# 13_Zynq_PL.net
KiCad netlist of a schematic drawn in Altium Designer
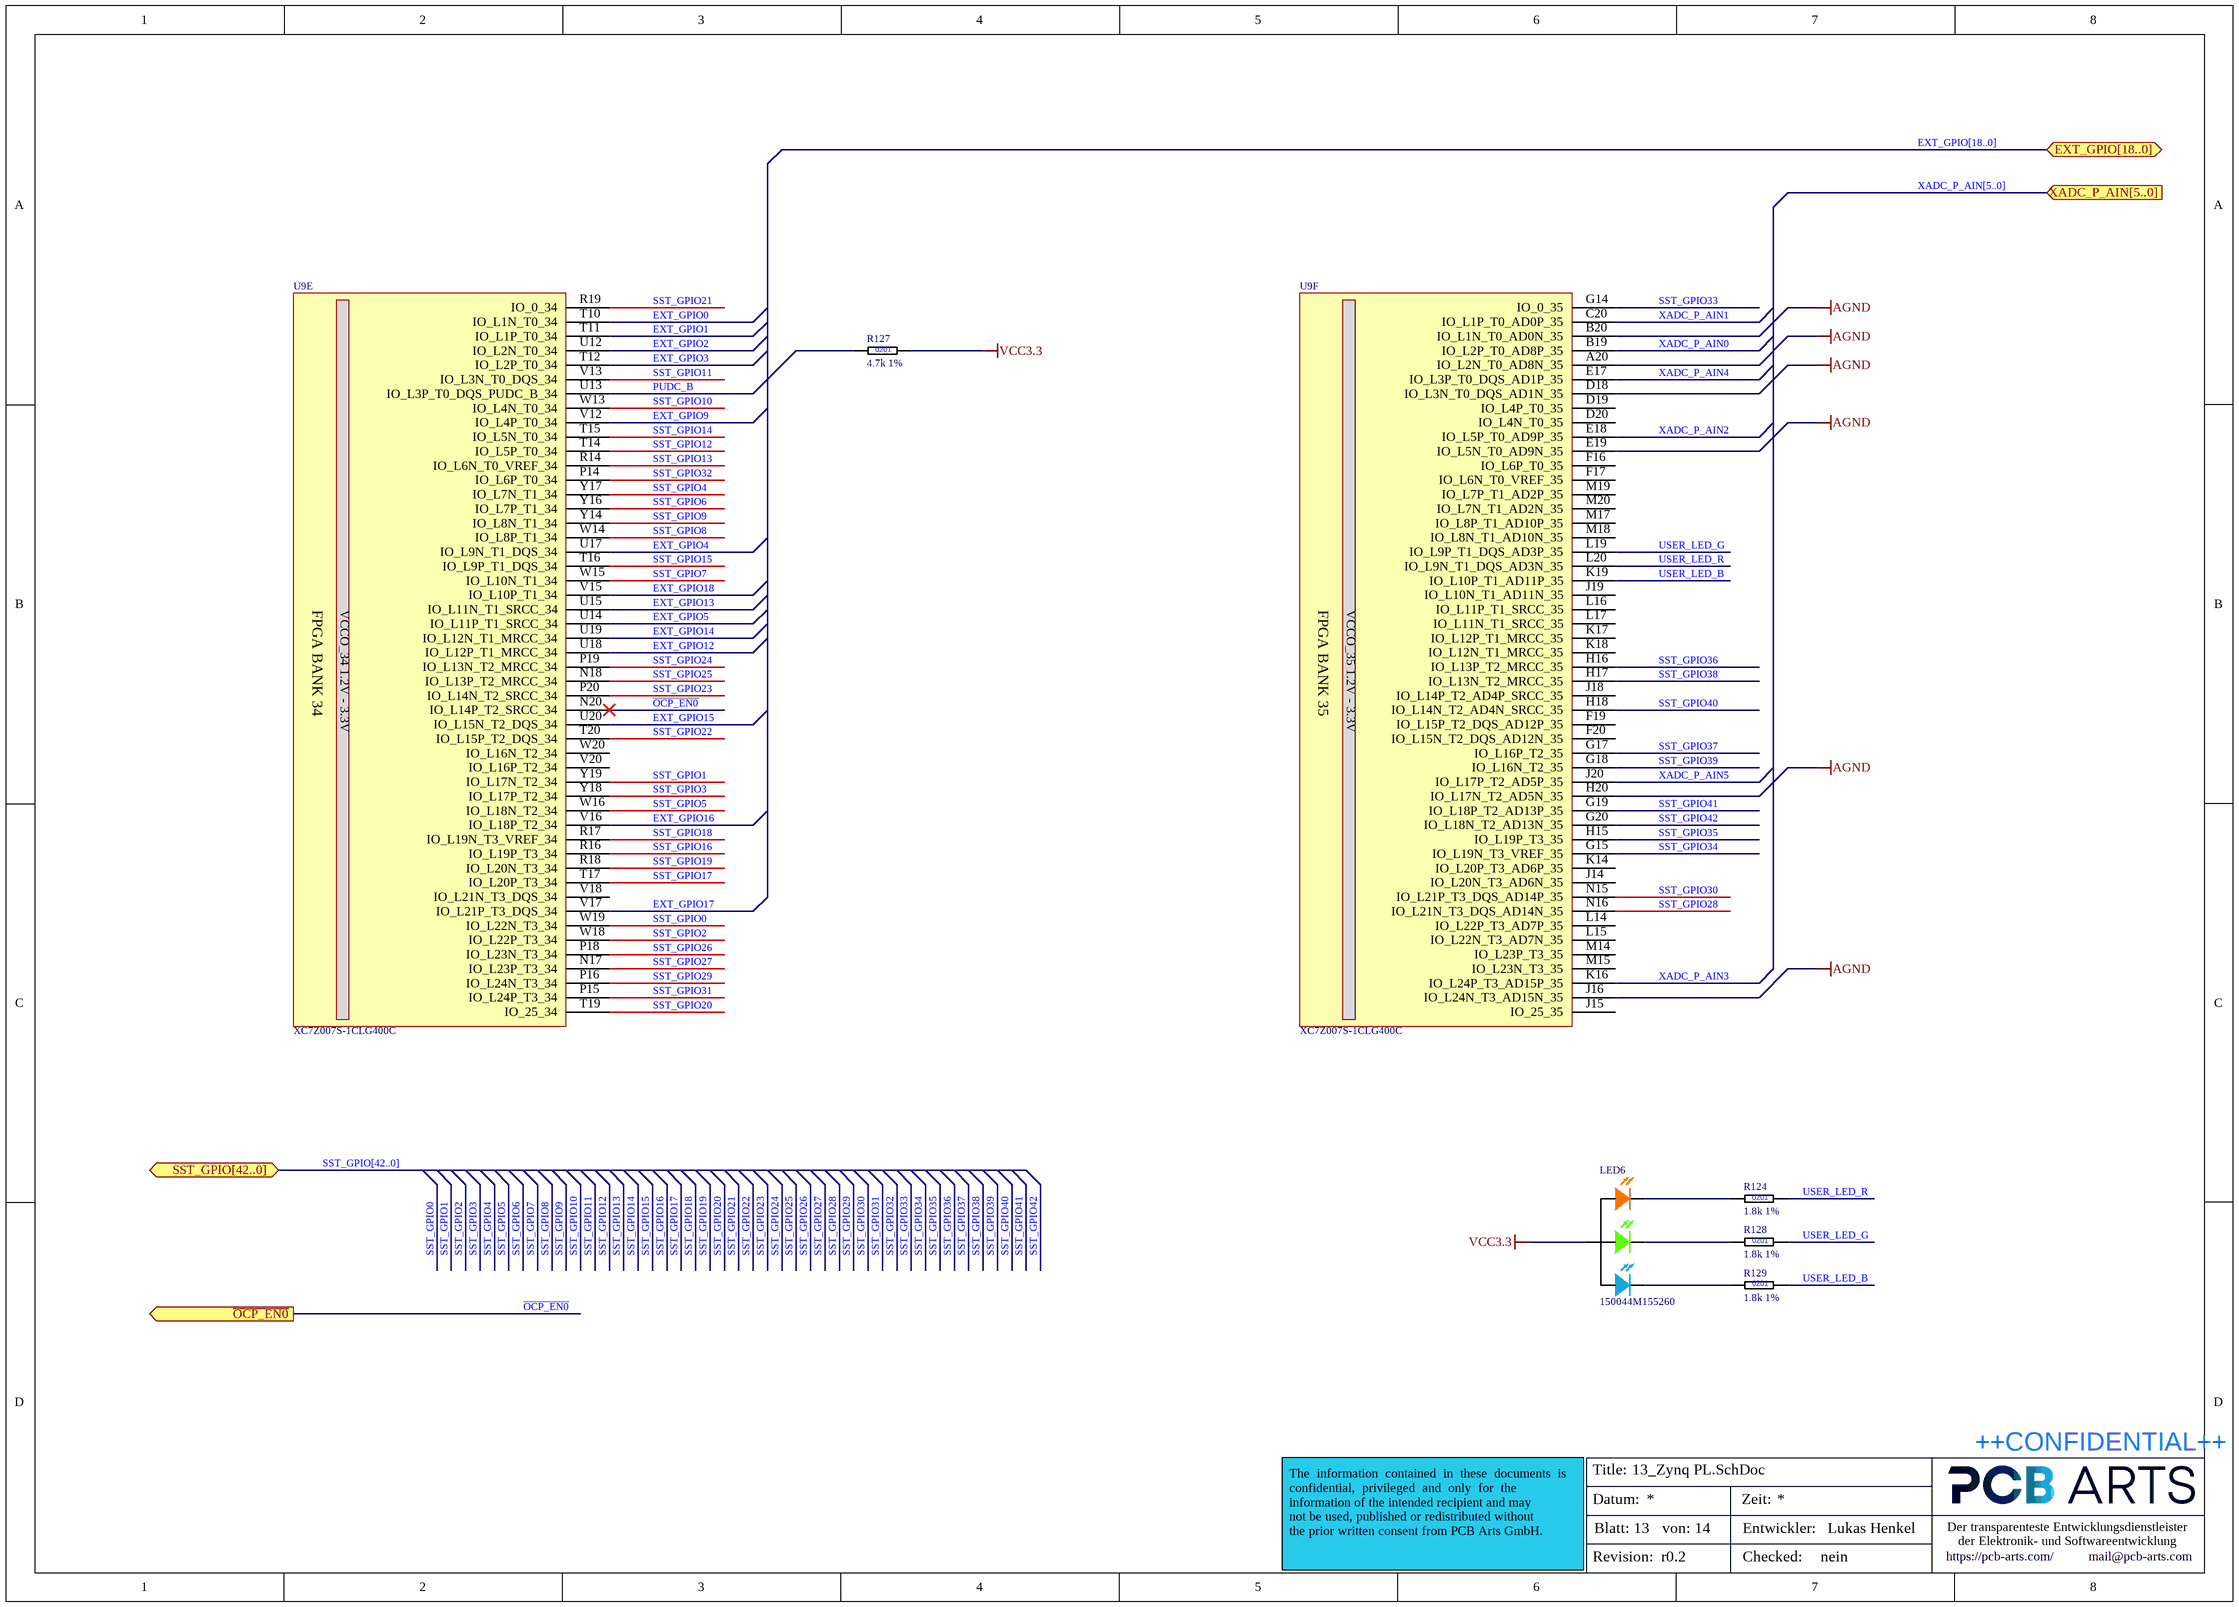
[diagram p0: 13_Zynq PL.SchDoc]

(export (version "E")
  (design (tool "Eeschema 10.0.6"))
  (components
    (comp (ref "LED6")
      (value "150044M155260")
      (footprint "Zynq-Feather-HD:WL-SFCC SMT")
      (description "Standard LEDs - SMD WL-SFCC SMT LED Full-color Chip")
      (libsource (lib "Zynq-Feather-HD") (part "150044M155260_SMD WL-SFCC SMT LED Full-color Chip"))
    )
    (comp (ref "R124")
      (value "1.8k 1%")
      (footprint "Zynq-Feather-HD:RESC0603X03L")
      (description "Thick Film Resistors - SMD 1.8K OHM 1%")
      (libsource (lib "Zynq-Feather-HD") (part "RES_0201_1.8k_1%"))
    )
    (comp (ref "R127")
      (value "4.7k 1%")
      (footprint "Zynq-Feather-HD:RESC0603X03L")
      (description "Thick Film Resistors - SMD 4.7K OHM 1%")
      (libsource (lib "Zynq-Feather-HD") (part "RES_0201_4.7k_1%"))
    )
    (comp (ref "R128")
      (value "1.8k 1%")
      (footprint "Zynq-Feather-HD:RESC0603X03L")
      (description "Thick Film Resistors - SMD 1.8K OHM 1%")
      (libsource (lib "Zynq-Feather-HD") (part "RES_0201_1.8k_1%"))
    )
    (comp (ref "R129")
      (value "1.8k 1%")
      (footprint "Zynq-Feather-HD:RESC0603X03L")
      (description "Thick Film Resistors - SMD 1.8K OHM 1%")
      (libsource (lib "Zynq-Feather-HD") (part "RES_0201_1.8k_1%"))
    )
    (comp (ref "U9")
      (value "XC7Z007S-1CLG400C")
      (footprint "Zynq-Feather-HD:BGA400C80P20X20_1700X1700X160")
      (description "XC7Z007S-1CLG400C_Processors - Application Specialised")
      (libsource (lib "Zynq-Feather-HD") (part "XC7Z007S-1CLG400C_Processors - Application Specialised"))
    )
  )
  (nets
    (net (code "6") (name "/EXT_GPIO0") (class "Default")
      (node (ref "U9") (pin "T10") (pinfunction "IO_L1N_T0_34_T10") (pintype "passive"))
    )
    (net (code "7") (name "/EXT_GPIO1") (class "Default")
      (node (ref "U9") (pin "T11") (pinfunction "IO_L1P_T0_34_T11") (pintype "passive"))
    )
    (net (code "8") (name "/EXT_GPIO2") (class "Default")
      (node (ref "U9") (pin "U12") (pinfunction "IO_L2N_T0_34_U12") (pintype "passive"))
    )
    (net (code "9") (name "/EXT_GPIO3") (class "Default")
      (node (ref "U9") (pin "T12") (pinfunction "IO_L2P_T0_34_T12") (pintype "passive"))
    )
    (net (code "10") (name "/EXT_GPIO4") (class "Default")
      (node (ref "U9") (pin "U17") (pinfunction "IO_L9N_T1_DQS_34_U17") (pintype "passive"))
    )
    (net (code "11") (name "/EXT_GPIO5") (class "Default")
      (node (ref "U9") (pin "U14") (pinfunction "IO_L11P_T1_SRCC_34_U14") (pintype "passive"))
    )
    (net (code "12") (name "/EXT_GPIO9") (class "Default")
      (node (ref "U9") (pin "V12") (pinfunction "IO_L4P_T0_34_V12") (pintype "passive"))
    )
    (net (code "13") (name "/EXT_GPIO12") (class "Default")
      (node (ref "U9") (pin "U18") (pinfunction "IO_L12P_T1_MRCC_34_U18") (pintype "passive"))
    )
    (net (code "14") (name "/EXT_GPIO13") (class "Default")
      (node (ref "U9") (pin "U15") (pinfunction "IO_L11N_T1_SRCC_34_U15") (pintype "passive"))
    )
    (net (code "15") (name "/EXT_GPIO14") (class "Default")
      (node (ref "U9") (pin "U19") (pinfunction "IO_L12N_T1_MRCC_34_U19") (pintype "passive"))
    )
    (net (code "16") (name "/EXT_GPIO15") (class "Default")
      (node (ref "U9") (pin "U20") (pinfunction "IO_L15N_T2_DQS_34_U20") (pintype "passive"))
    )
    (net (code "17") (name "/EXT_GPIO16") (class "Default")
      (node (ref "U9") (pin "V16") (pinfunction "IO_L18P_T2_34_V16") (pintype "passive"))
    )
    (net (code "18") (name "/EXT_GPIO17") (class "Default")
      (node (ref "U9") (pin "V17") (pinfunction "IO_L21P_T3_DQS_34_V17") (pintype "passive"))
    )
    (net (code "19") (name "/EXT_GPIO18") (class "Default")
      (node (ref "U9") (pin "V15") (pinfunction "IO_L10P_T1_34_V15") (pintype "passive"))
    )
    (net (code "21") (name "/PUDC_B") (class "Default")
      (node (ref "R127") (pin "1") (pinfunction "1_1") (pintype "passive"))
      (node (ref "U9") (pin "U13") (pinfunction "IO_L3P_T0_DQS_PUDC_B_34_U13") (pintype "passive"))
    )
    (net (code "22") (name "/SST_GPIO0") (class "Default")
      (node (ref "U9") (pin "W19") (pinfunction "IO_L22N_T3_34_W19") (pintype "passive"))
    )
    (net (code "23") (name "/SST_GPIO1") (class "Default")
      (node (ref "U9") (pin "Y19") (pinfunction "IO_L17N_T2_34_Y19") (pintype "passive"))
    )
    (net (code "24") (name "/SST_GPIO2") (class "Default")
      (node (ref "U9") (pin "W18") (pinfunction "IO_L22P_T3_34_W18") (pintype "passive"))
    )
    (net (code "25") (name "/SST_GPIO3") (class "Default")
      (node (ref "U9") (pin "Y18") (pinfunction "IO_L17P_T2_34_Y18") (pintype "passive"))
    )
    (net (code "26") (name "/SST_GPIO4") (class "Default")
      (node (ref "U9") (pin "Y17") (pinfunction "IO_L7N_T1_34_Y17") (pintype "passive"))
    )
    (net (code "27") (name "/SST_GPIO5") (class "Default")
      (node (ref "U9") (pin "W16") (pinfunction "IO_L18N_T2_34_W16") (pintype "passive"))
    )
    (net (code "28") (name "/SST_GPIO6") (class "Default")
      (node (ref "U9") (pin "Y16") (pinfunction "IO_L7P_T1_34_Y16") (pintype "passive"))
    )
    (net (code "29") (name "/SST_GPIO7") (class "Default")
      (node (ref "U9") (pin "W15") (pinfunction "IO_L10N_T1_34_W15") (pintype "passive"))
    )
    (net (code "30") (name "/SST_GPIO8") (class "Default")
      (node (ref "U9") (pin "W14") (pinfunction "IO_L8P_T1_34_W14") (pintype "passive"))
    )
    (net (code "31") (name "/SST_GPIO9") (class "Default")
      (node (ref "U9") (pin "Y14") (pinfunction "IO_L8N_T1_34_Y14") (pintype "passive"))
    )
    (net (code "32") (name "/SST_GPIO10") (class "Default")
      (node (ref "U9") (pin "W13") (pinfunction "IO_L4N_T0_34_W13") (pintype "passive"))
    )
    (net (code "33") (name "/SST_GPIO11") (class "Default")
      (node (ref "U9") (pin "V13") (pinfunction "IO_L3N_T0_DQS_34_V13") (pintype "passive"))
    )
    (net (code "34") (name "/SST_GPIO12") (class "Default")
      (node (ref "U9") (pin "T14") (pinfunction "IO_L5P_T0_34_T14") (pintype "passive"))
    )
    (net (code "35") (name "/SST_GPIO13") (class "Default")
      (node (ref "U9") (pin "R14") (pinfunction "IO_L6N_T0_VREF_34_R14") (pintype "passive"))
    )
    (net (code "36") (name "/SST_GPIO14") (class "Default")
      (node (ref "U9") (pin "T15") (pinfunction "IO_L5N_T0_34_T15") (pintype "passive"))
    )
    (net (code "37") (name "/SST_GPIO15") (class "Default")
      (node (ref "U9") (pin "T16") (pinfunction "IO_L9P_T1_DQS_34_T16") (pintype "passive"))
    )
    (net (code "38") (name "/SST_GPIO16") (class "Default")
      (node (ref "U9") (pin "R16") (pinfunction "IO_L19P_T3_34_R16") (pintype "passive"))
    )
    (net (code "39") (name "/SST_GPIO17") (class "Default")
      (node (ref "U9") (pin "T17") (pinfunction "IO_L20P_T3_34_T17") (pintype "passive"))
    )
    (net (code "40") (name "/SST_GPIO18") (class "Default")
      (node (ref "U9") (pin "R17") (pinfunction "IO_L19N_T3_VREF_34_R17") (pintype "passive"))
    )
    (net (code "41") (name "/SST_GPIO19") (class "Default")
      (node (ref "U9") (pin "R18") (pinfunction "IO_L20N_T3_34_R18") (pintype "passive"))
    )
    (net (code "42") (name "/SST_GPIO20") (class "Default")
      (node (ref "U9") (pin "T19") (pinfunction "IO_25_34_T19") (pintype "passive"))
    )
    (net (code "43") (name "/SST_GPIO21") (class "Default")
      (node (ref "U9") (pin "R19") (pinfunction "IO_0_34_R19") (pintype "passive"))
    )
    (net (code "44") (name "/SST_GPIO22") (class "Default")
      (node (ref "U9") (pin "T20") (pinfunction "IO_L15P_T2_DQS_34_T20") (pintype "passive"))
    )
    (net (code "45") (name "/SST_GPIO23") (class "Default")
      (node (ref "U9") (pin "P20") (pinfunction "IO_L14N_T2_SRCC_34_P20") (pintype "passive"))
    )
    (net (code "46") (name "/SST_GPIO24") (class "Default")
      (node (ref "U9") (pin "P19") (pinfunction "IO_L13N_T2_MRCC_34_P19") (pintype "passive"))
    )
    (net (code "47") (name "/SST_GPIO25") (class "Default")
      (node (ref "U9") (pin "N18") (pinfunction "IO_L13P_T2_MRCC_34_N18") (pintype "passive"))
    )
    (net (code "48") (name "/SST_GPIO26") (class "Default")
      (node (ref "U9") (pin "P18") (pinfunction "IO_L23N_T3_34_P18") (pintype "passive"))
    )
    (net (code "49") (name "/SST_GPIO27") (class "Default")
      (node (ref "U9") (pin "N17") (pinfunction "IO_L23P_T3_34_N17") (pintype "passive"))
    )
    (net (code "50") (name "/SST_GPIO28") (class "Default")
      (node (ref "U9") (pin "N16") (pinfunction "IO_L21N_T3_DQS_AD14N_35_N16") (pintype "passive"))
    )
    (net (code "51") (name "/SST_GPIO29") (class "Default")
      (node (ref "U9") (pin "P16") (pinfunction "IO_L24N_T3_34_P16") (pintype "passive"))
    )
    (net (code "52") (name "/SST_GPIO30") (class "Default")
      (node (ref "U9") (pin "N15") (pinfunction "IO_L21P_T3_DQS_AD14P_35_N15") (pintype "passive"))
    )
    (net (code "53") (name "/SST_GPIO31") (class "Default")
      (node (ref "U9") (pin "P15") (pinfunction "IO_L24P_T3_34_P15") (pintype "passive"))
    )
    (net (code "54") (name "/SST_GPIO32") (class "Default")
      (node (ref "U9") (pin "P14") (pinfunction "IO_L6P_T0_34_P14") (pintype "passive"))
    )
    (net (code "55") (name "/SST_GPIO33") (class "Default")
      (node (ref "U9") (pin "G14") (pinfunction "IO_0_35_G14") (pintype "passive"))
    )
    (net (code "56") (name "/SST_GPIO34") (class "Default")
      (node (ref "U9") (pin "G15") (pinfunction "IO_L19N_T3_VREF_35_G15") (pintype "passive"))
    )
    (net (code "57") (name "/SST_GPIO35") (class "Default")
      (node (ref "U9") (pin "H15") (pinfunction "IO_L19P_T3_35_H15") (pintype "passive"))
    )
    (net (code "58") (name "/SST_GPIO36") (class "Default")
      (node (ref "U9") (pin "H16") (pinfunction "IO_L13P_T2_MRCC_35_H16") (pintype "passive"))
    )
    (net (code "59") (name "/SST_GPIO37") (class "Default")
      (node (ref "U9") (pin "G17") (pinfunction "IO_L16P_T2_35_G17") (pintype "passive"))
    )
    (net (code "60") (name "/SST_GPIO38") (class "Default")
      (node (ref "U9") (pin "H17") (pinfunction "IO_L13N_T2_MRCC_35_H17") (pintype "passive"))
    )
    (net (code "61") (name "/SST_GPIO39") (class "Default")
      (node (ref "U9") (pin "G18") (pinfunction "IO_L16N_T2_35_G18") (pintype "passive"))
    )
    (net (code "62") (name "/SST_GPIO40") (class "Default")
      (node (ref "U9") (pin "H18") (pinfunction "IO_L14N_T2_AD4N_SRCC_35_H18") (pintype "passive"))
    )
    (net (code "63") (name "/SST_GPIO41") (class "Default")
      (node (ref "U9") (pin "G19") (pinfunction "IO_L18P_T2_AD13P_35_G19") (pintype "passive"))
    )
    (net (code "64") (name "/SST_GPIO42") (class "Default")
      (node (ref "U9") (pin "G20") (pinfunction "IO_L18N_T2_AD13N_35_G20") (pintype "passive"))
    )
    (net (code "66") (name "/USER_LED_B") (class "Default")
      (node (ref "R129") (pin "2") (pinfunction "2_2") (pintype "passive"))
      (node (ref "U9") (pin "K19") (pinfunction "IO_L10P_T1_AD11P_35_K19") (pintype "passive"))
    )
    (net (code "67") (name "/USER_LED_G") (class "Default")
      (node (ref "R128") (pin "2") (pinfunction "2_2") (pintype "passive"))
      (node (ref "U9") (pin "L19") (pinfunction "IO_L9P_T1_DQS_AD3P_35_L19") (pintype "passive"))
    )
    (net (code "68") (name "/USER_LED_R") (class "Default")
      (node (ref "R124") (pin "2") (pinfunction "2_2") (pintype "passive"))
      (node (ref "U9") (pin "L20") (pinfunction "IO_L9N_T1_DQS_AD3N_35_L20") (pintype "passive"))
    )
    (net (code "69") (name "/XADC_P_AIN0") (class "Default")
      (node (ref "U9") (pin "B19") (pinfunction "IO_L2P_T0_AD8P_35_B19") (pintype "passive"))
    )
    (net (code "70") (name "/XADC_P_AIN1") (class "Default")
      (node (ref "U9") (pin "C20") (pinfunction "IO_L1P_T0_AD0P_35_C20") (pintype "passive"))
    )
    (net (code "71") (name "/XADC_P_AIN2") (class "Default")
      (node (ref "U9") (pin "E18") (pinfunction "IO_L5P_T0_AD9P_35_E18") (pintype "passive"))
    )
    (net (code "72") (name "/XADC_P_AIN3") (class "Default")
      (node (ref "U9") (pin "K16") (pinfunction "IO_L24P_T3_AD15P_35_K16") (pintype "passive"))
    )
    (net (code "73") (name "/XADC_P_AIN4") (class "Default")
      (node (ref "U9") (pin "E17") (pinfunction "IO_L3P_T0_DQS_AD1P_35_E17") (pintype "passive"))
    )
    (net (code "74") (name "/XADC_P_AIN5") (class "Default")
      (node (ref "U9") (pin "J20") (pinfunction "IO_L17P_T2_AD5P_35_J20") (pintype "passive"))
    )
    (net (code "76") (name "/~{OCP_EN0}") (class "Default")
      (node (ref "U9") (pin "N20") (pinfunction "IO_L14P_T2_SRCC_34_N20") (pintype "passive"))
    )
    (net (code "77") (name "AGND") (class "Default")
      (node (ref "U9") (pin "A20") (pinfunction "IO_L2N_T0_AD8N_35_A20") (pintype "passive"))
      (node (ref "U9") (pin "B20") (pinfunction "IO_L1N_T0_AD0N_35_B20") (pintype "passive"))
      (node (ref "U9") (pin "D18") (pinfunction "IO_L3N_T0_DQS_AD1N_35_D18") (pintype "passive"))
      (node (ref "U9") (pin "E19") (pinfunction "IO_L5N_T0_AD9N_35_E19") (pintype "passive"))
      (node (ref "U9") (pin "H20") (pinfunction "IO_L17N_T2_AD5N_35_H20") (pintype "passive"))
      (node (ref "U9") (pin "J16") (pinfunction "IO_L24N_T3_AD15N_35_J16") (pintype "passive"))
    )
    (net (code "78") (name "Net-(LED6-Pad2)") (class "Default")
      (node (ref "LED6") (pin "2") (pinfunction "2_2") (pintype "passive"))
      (node (ref "R124") (pin "1") (pinfunction "1_1") (pintype "passive"))
    )
    (net (code "79") (name "Net-(LED6-Pad3)") (class "Default")
      (node (ref "LED6") (pin "3") (pinfunction "3_3") (pintype "passive"))
      (node (ref "R128") (pin "1") (pinfunction "1_1") (pintype "passive"))
    )
    (net (code "80") (name "Net-(LED6-Pad4)") (class "Default")
      (node (ref "LED6") (pin "4") (pinfunction "4_4") (pintype "passive"))
      (node (ref "R129") (pin "1") (pinfunction "1_1") (pintype "passive"))
    )
    (net (code "81") (name "VCC3.3") (class "Default")
      (node (ref "LED6") (pin "1") (pinfunction "1_1") (pintype "passive"))
      (node (ref "R127") (pin "2") (pinfunction "2_2") (pintype "passive"))
    )
    (net (code "82") (name "unconnected-(U9E-IO_L16N_T2_34-PadW20)") (class "Default")
      (node (ref "U9") (pin "W20") (pinfunction "IO_L16N_T2_34_W20") (pintype "passive"))
    )
    (net (code "83") (name "unconnected-(U9E-IO_L16P_T2_34-PadV20)") (class "Default")
      (node (ref "U9") (pin "V20") (pinfunction "IO_L16P_T2_34_V20") (pintype "passive"))
    )
    (net (code "84") (name "unconnected-(U9E-IO_L21N_T3_DQS_34-PadV18)") (class "Default")
      (node (ref "U9") (pin "V18") (pinfunction "IO_L21N_T3_DQS_34_V18") (pintype "passive"))
    )
    (net (code "85") (name "unconnected-(U9F-IO_25_35-PadJ15)") (class "Default")
      (node (ref "U9") (pin "J15") (pinfunction "IO_25_35_J15") (pintype "passive"))
    )
    (net (code "86") (name "unconnected-(U9F-IO_L4N_T0_35-PadD20)") (class "Default")
      (node (ref "U9") (pin "D20") (pinfunction "IO_L4N_T0_35_D20") (pintype "passive"))
    )
    (net (code "87") (name "unconnected-(U9F-IO_L4P_T0_35-PadD19)") (class "Default")
      (node (ref "U9") (pin "D19") (pinfunction "IO_L4P_T0_35_D19") (pintype "passive"))
    )
    (net (code "88") (name "unconnected-(U9F-IO_L6N_T0_VREF_35-PadF17)") (class "Default")
      (node (ref "U9") (pin "F17") (pinfunction "IO_L6N_T0_VREF_35_F17") (pintype "passive"))
    )
    (net (code "89") (name "unconnected-(U9F-IO_L6P_T0_35-PadF16)") (class "Default")
      (node (ref "U9") (pin "F16") (pinfunction "IO_L6P_T0_35_F16") (pintype "passive"))
    )
    (net (code "90") (name "unconnected-(U9F-IO_L7N_T1_AD2N_35-PadM20)") (class "Default")
      (node (ref "U9") (pin "M20") (pinfunction "IO_L7N_T1_AD2N_35_M20") (pintype "passive"))
    )
    (net (code "91") (name "unconnected-(U9F-IO_L7P_T1_AD2P_35-PadM19)") (class "Default")
      (node (ref "U9") (pin "M19") (pinfunction "IO_L7P_T1_AD2P_35_M19") (pintype "passive"))
    )
    (net (code "92") (name "unconnected-(U9F-IO_L8N_T1_AD10N_35-PadM18)") (class "Default")
      (node (ref "U9") (pin "M18") (pinfunction "IO_L8N_T1_AD10N_35_M18") (pintype "passive"))
    )
    (net (code "93") (name "unconnected-(U9F-IO_L8P_T1_AD10P_35-PadM17)") (class "Default")
      (node (ref "U9") (pin "M17") (pinfunction "IO_L8P_T1_AD10P_35_M17") (pintype "passive"))
    )
    (net (code "94") (name "unconnected-(U9F-IO_L10N_T1_AD11N_35-PadJ19)") (class "Default")
      (node (ref "U9") (pin "J19") (pinfunction "IO_L10N_T1_AD11N_35_J19") (pintype "passive"))
    )
    (net (code "95") (name "unconnected-(U9F-IO_L11N_T1_SRCC_35-PadL17)") (class "Default")
      (node (ref "U9") (pin "L17") (pinfunction "IO_L11N_T1_SRCC_35_L17") (pintype "passive"))
    )
    (net (code "96") (name "unconnected-(U9F-IO_L11P_T1_SRCC_35-PadL16)") (class "Default")
      (node (ref "U9") (pin "L16") (pinfunction "IO_L11P_T1_SRCC_35_L16") (pintype "passive"))
    )
    (net (code "97") (name "unconnected-(U9F-IO_L12N_T1_MRCC_35-PadK18)") (class "Default")
      (node (ref "U9") (pin "K18") (pinfunction "IO_L12N_T1_MRCC_35_K18") (pintype "passive"))
    )
    (net (code "98") (name "unconnected-(U9F-IO_L12P_T1_MRCC_35-PadK17)") (class "Default")
      (node (ref "U9") (pin "K17") (pinfunction "IO_L12P_T1_MRCC_35_K17") (pintype "passive"))
    )
    (net (code "99") (name "unconnected-(U9F-IO_L14P_T2_AD4P_SRCC_35-PadJ18)") (class "Default")
      (node (ref "U9") (pin "J18") (pinfunction "IO_L14P_T2_AD4P_SRCC_35_J18") (pintype "passive"))
    )
    (net (code "100") (name "unconnected-(U9F-IO_L15N_T2_DQS_AD12N_35-PadF20)") (class "Default")
      (node (ref "U9") (pin "F20") (pinfunction "IO_L15N_T2_DQS_AD12N_35_F20") (pintype "passive"))
    )
    (net (code "101") (name "unconnected-(U9F-IO_L15P_T2_DQS_AD12P_35-PadF19)") (class "Default")
      (node (ref "U9") (pin "F19") (pinfunction "IO_L15P_T2_DQS_AD12P_35_F19") (pintype "passive"))
    )
    (net (code "102") (name "unconnected-(U9F-IO_L20N_T3_AD6N_35-PadJ14)") (class "Default")
      (node (ref "U9") (pin "J14") (pinfunction "IO_L20N_T3_AD6N_35_J14") (pintype "passive"))
    )
    (net (code "103") (name "unconnected-(U9F-IO_L20P_T3_AD6P_35-PadK14)") (class "Default")
      (node (ref "U9") (pin "K14") (pinfunction "IO_L20P_T3_AD6P_35_K14") (pintype "passive"))
    )
    (net (code "104") (name "unconnected-(U9F-IO_L22N_T3_AD7N_35-PadL15)") (class "Default")
      (node (ref "U9") (pin "L15") (pinfunction "IO_L22N_T3_AD7N_35_L15") (pintype "passive"))
    )
    (net (code "105") (name "unconnected-(U9F-IO_L22P_T3_AD7P_35-PadL14)") (class "Default")
      (node (ref "U9") (pin "L14") (pinfunction "IO_L22P_T3_AD7P_35_L14") (pintype "passive"))
    )
    (net (code "106") (name "unconnected-(U9F-IO_L23N_T3_35-PadM15)") (class "Default")
      (node (ref "U9") (pin "M15") (pinfunction "IO_L23N_T3_35_M15") (pintype "passive"))
    )
    (net (code "107") (name "unconnected-(U9F-IO_L23P_T3_35-PadM14)") (class "Default")
      (node (ref "U9") (pin "M14") (pinfunction "IO_L23P_T3_35_M14") (pintype "passive"))
    )
  )
)
